# HW1_1_b.net
KiCad netlist of a schematic drawn in EasyEDA
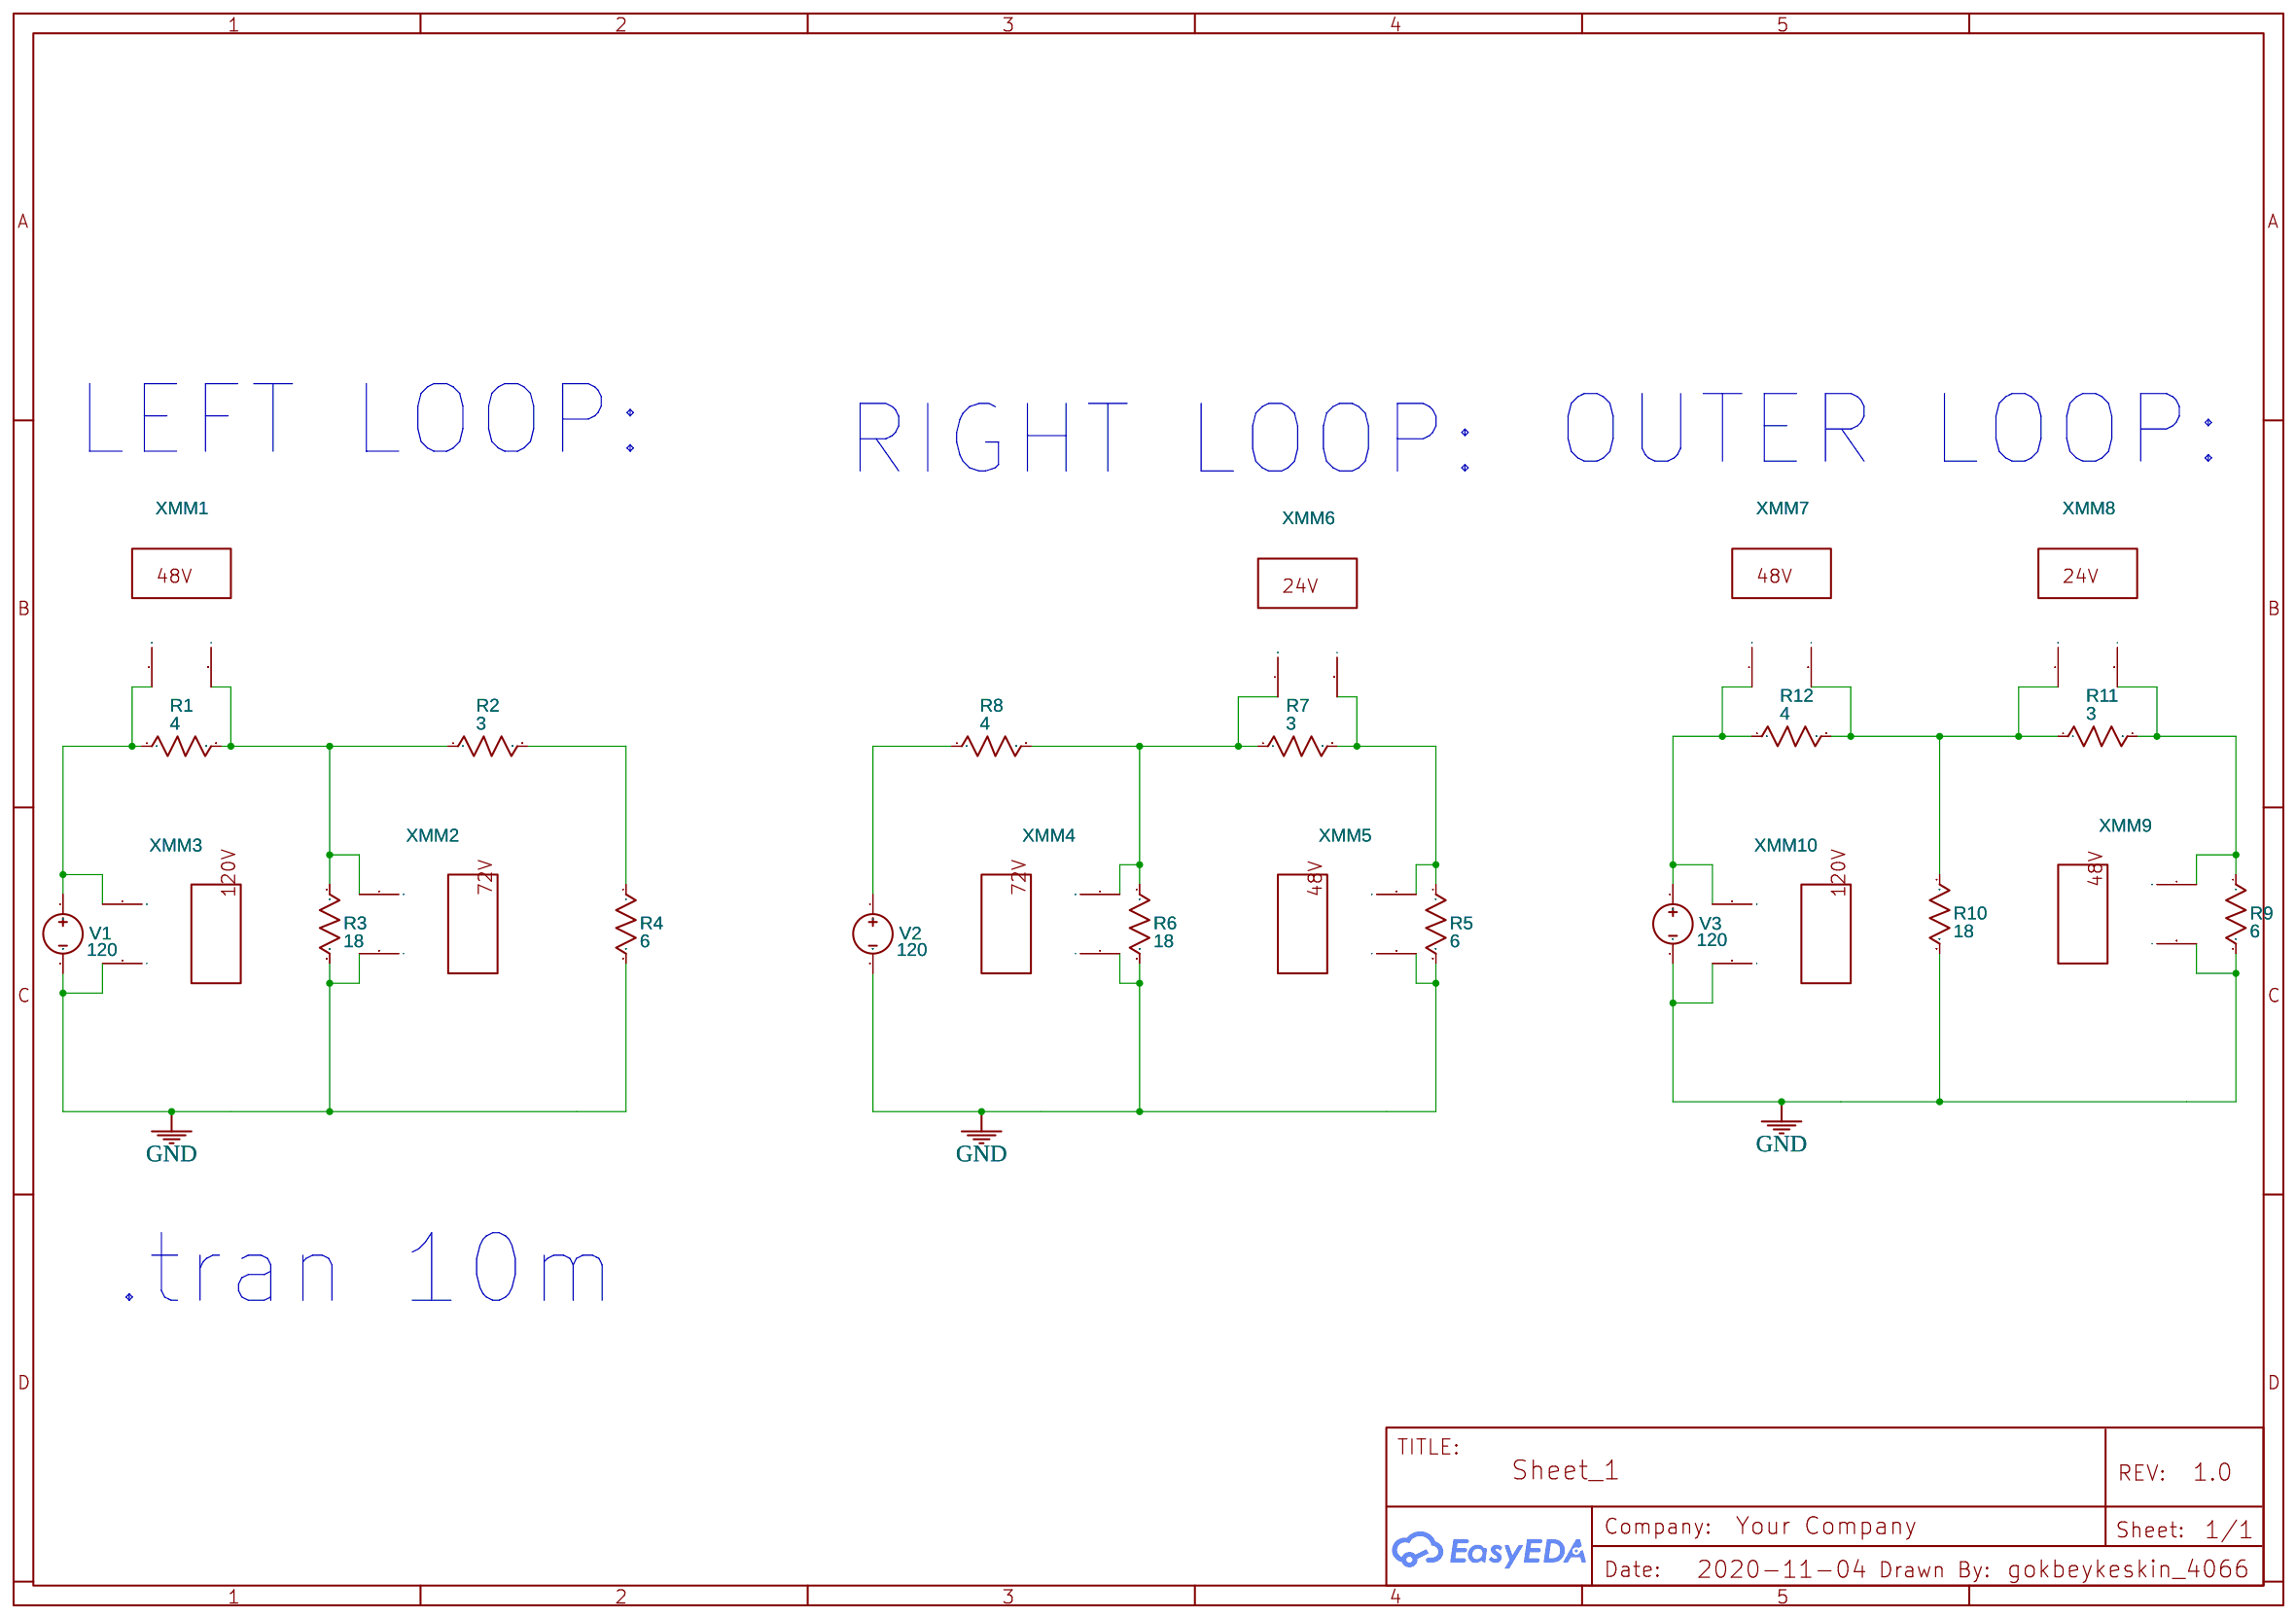
[diagram p0: schematic sheet]

(export (version "E")
  (design (tool "Eeschema 10.0.6"))
  (components
    (comp (ref "R1") (value "4") (libsource (lib "") (part "Resistor_US")))
    (comp (ref "R2") (value "3") (libsource (lib "") (part "Resistor_US")))
    (comp (ref "R3") (value "18") (libsource (lib "") (part "Resistor_US_1")))
    (comp (ref "R4") (value "6") (libsource (lib "") (part "Resistor_US_1")))
    (comp (ref "R5") (value "6") (libsource (lib "") (part "Resistor_US_1")))
    (comp (ref "R6") (value "18") (libsource (lib "") (part "Resistor_US_1")))
    (comp (ref "R7") (value "3") (libsource (lib "") (part "Resistor_US")))
    (comp (ref "R8") (value "4") (libsource (lib "") (part "Resistor_US")))
    (comp (ref "R9") (value "6") (libsource (lib "") (part "Resistor_US_1")))
    (comp (ref "R10") (value "18") (libsource (lib "") (part "Resistor_US_1")))
    (comp (ref "R11") (value "3") (libsource (lib "") (part "Resistor_US")))
    (comp (ref "R12") (value "4") (libsource (lib "") (part "Resistor_US")))
    (comp (ref "V1") (value "120") (libsource (lib "") (part "VDC")))
    (comp (ref "V2") (value "120") (libsource (lib "") (part "VDC")))
    (comp (ref "V3") (value "120") (libsource (lib "") (part "VDC")))
    (comp (ref "XMM1") (value "Multimeter") (libsource (lib "") (part "MULTIMETER")))
    (comp (ref "XMM2") (value "Multimeter") (libsource (lib "") (part "MULTIMETER_4")))
    (comp (ref "XMM3") (value "Multimeter") (libsource (lib "") (part "MULTIMETER_5")))
    (comp (ref "XMM4") (value "Multimeter") (libsource (lib "") (part "MULTIMETER_3")))
    (comp (ref "XMM5") (value "Multimeter") (libsource (lib "") (part "MULTIMETER_1")))
    (comp (ref "XMM6") (value "Multimeter") (libsource (lib "") (part "MULTIMETER_2")))
    (comp (ref "XMM7") (value "Multimeter") (libsource (lib "") (part "MULTIMETER")))
    (comp (ref "XMM8") (value "Multimeter") (libsource (lib "") (part "MULTIMETER_2")))
    (comp (ref "XMM9") (value "Multimeter") (libsource (lib "") (part "MULTIMETER_1")))
    (comp (ref "XMM10") (value "Multimeter") (libsource (lib "") (part "MULTIMETER_5")))
  )
  (nets
    (net (code "1") (name "GND") (class "Default")
      (node (ref "R10") (pin "2") (pinfunction "2_2") (pintype "unspecified"))
      (node (ref "R3") (pin "2") (pinfunction "2_2") (pintype "unspecified"))
      (node (ref "R4") (pin "2") (pinfunction "2_2") (pintype "unspecified"))
      (node (ref "R5") (pin "2") (pinfunction "2_2") (pintype "unspecified"))
      (node (ref "R6") (pin "2") (pinfunction "2_2") (pintype "unspecified"))
      (node (ref "R9") (pin "2") (pinfunction "2_2") (pintype "unspecified"))
      (node (ref "V1") (pin "2") (pinfunction "2_2") (pintype "unspecified"))
      (node (ref "V2") (pin "2") (pinfunction "2_2") (pintype "unspecified"))
      (node (ref "V3") (pin "2") (pinfunction "2_2") (pintype "unspecified"))
      (node (ref "XMM10") (pin "2") (pinfunction "I_2") (pintype "unspecified"))
      (node (ref "XMM2") (pin "2") (pinfunction "I_2") (pintype "unspecified"))
      (node (ref "XMM3") (pin "2") (pinfunction "I_2") (pintype "unspecified"))
      (node (ref "XMM4") (pin "2") (pinfunction "I_2") (pintype "unspecified"))
      (node (ref "XMM5") (pin "2") (pinfunction "I_2") (pintype "unspecified"))
      (node (ref "XMM9") (pin "2") (pinfunction "I_2") (pintype "unspecified"))
    )
    (net (code "2") (name "Net-(R2-Pad2)") (class "Default")
      (node (ref "R2") (pin "2") (pinfunction "2_2") (pintype "unspecified"))
      (node (ref "R4") (pin "1") (pinfunction "1_1") (pintype "unspecified"))
    )
    (net (code "3") (name "Net-(R8-Pad1)") (class "Default")
      (node (ref "R8") (pin "1") (pinfunction "1_1") (pintype "unspecified"))
      (node (ref "V2") (pin "1") (pinfunction "1_1") (pintype "unspecified"))
    )
    (net (code "4") (name "Net-(XMM1-+)") (class "Default")
      (node (ref "R1") (pin "1") (pinfunction "1_1") (pintype "unspecified"))
      (node (ref "V1") (pin "1") (pinfunction "1_1") (pintype "unspecified"))
      (node (ref "XMM1") (pin "1") (pinfunction "+_1") (pintype "unspecified"))
      (node (ref "XMM3") (pin "1") (pinfunction "+_1") (pintype "unspecified"))
    )
    (net (code "5") (name "Net-(XMM1-I)") (class "Default")
      (node (ref "R1") (pin "2") (pinfunction "2_2") (pintype "unspecified"))
      (node (ref "R2") (pin "1") (pinfunction "1_1") (pintype "unspecified"))
      (node (ref "R3") (pin "1") (pinfunction "1_1") (pintype "unspecified"))
      (node (ref "XMM1") (pin "2") (pinfunction "I_2") (pintype "unspecified"))
      (node (ref "XMM2") (pin "1") (pinfunction "+_1") (pintype "unspecified"))
    )
    (net (code "6") (name "Net-(XMM4-+)") (class "Default")
      (node (ref "R6") (pin "1") (pinfunction "1_1") (pintype "unspecified"))
      (node (ref "R7") (pin "1") (pinfunction "1_1") (pintype "unspecified"))
      (node (ref "R8") (pin "2") (pinfunction "2_2") (pintype "unspecified"))
      (node (ref "XMM4") (pin "1") (pinfunction "+_1") (pintype "unspecified"))
      (node (ref "XMM6") (pin "1") (pinfunction "+_1") (pintype "unspecified"))
    )
    (net (code "7") (name "Net-(XMM5-+)") (class "Default")
      (node (ref "R5") (pin "1") (pinfunction "1_1") (pintype "unspecified"))
      (node (ref "R7") (pin "2") (pinfunction "2_2") (pintype "unspecified"))
      (node (ref "XMM5") (pin "1") (pinfunction "+_1") (pintype "unspecified"))
      (node (ref "XMM6") (pin "2") (pinfunction "I_2") (pintype "unspecified"))
    )
    (net (code "8") (name "Net-(XMM7-I)") (class "Default")
      (node (ref "R10") (pin "1") (pinfunction "1_1") (pintype "unspecified"))
      (node (ref "R11") (pin "1") (pinfunction "1_1") (pintype "unspecified"))
      (node (ref "R12") (pin "2") (pinfunction "2_2") (pintype "unspecified"))
      (node (ref "XMM7") (pin "2") (pinfunction "I_2") (pintype "unspecified"))
      (node (ref "XMM8") (pin "1") (pinfunction "+_1") (pintype "unspecified"))
    )
    (net (code "9") (name "Net-(XMM8-I)") (class "Default")
      (node (ref "R11") (pin "2") (pinfunction "2_2") (pintype "unspecified"))
      (node (ref "R9") (pin "1") (pinfunction "1_1") (pintype "unspecified"))
      (node (ref "XMM8") (pin "2") (pinfunction "I_2") (pintype "unspecified"))
      (node (ref "XMM9") (pin "1") (pinfunction "+_1") (pintype "unspecified"))
    )
    (net (code "10") (name "Net-(XMM10-+)") (class "Default")
      (node (ref "R12") (pin "1") (pinfunction "1_1") (pintype "unspecified"))
      (node (ref "V3") (pin "1") (pinfunction "1_1") (pintype "unspecified"))
      (node (ref "XMM10") (pin "1") (pinfunction "+_1") (pintype "unspecified"))
      (node (ref "XMM7") (pin "1") (pinfunction "+_1") (pintype "unspecified"))
    )
  )
)
